# P08_eMMC.net
KiCad netlist of a schematic drawn in Altium Designer
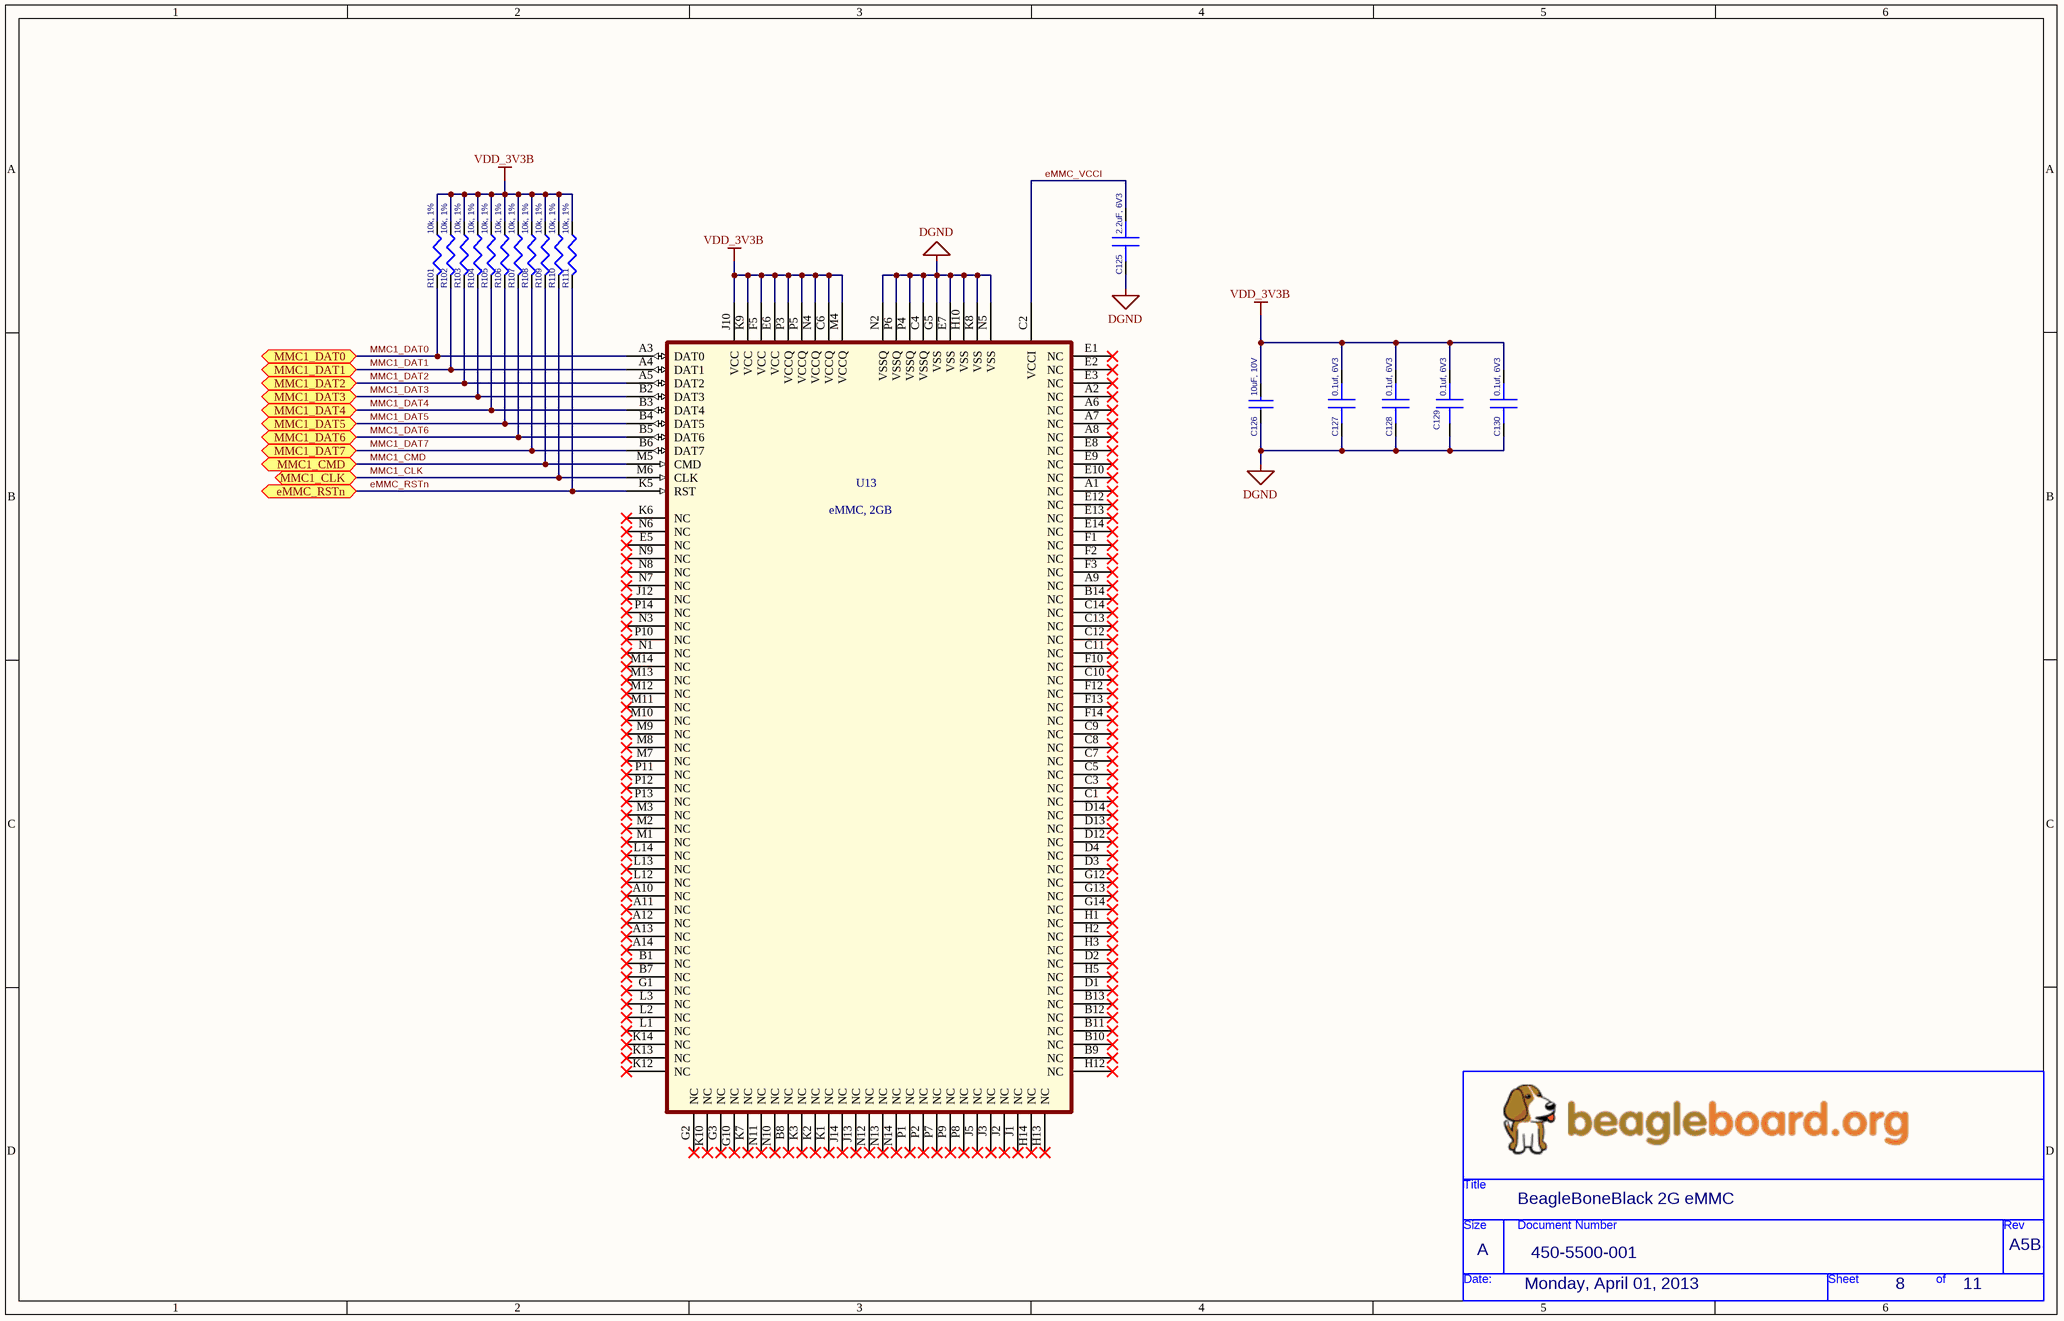
[diagram p0: P08_eMMC.SchDoc]

(export (version "E")
  (design (tool "Eeschema 10.0.6"))
  (components
    (comp (ref "C125")
      (value "2.2uF, 6V3")
      (footprint "402")
      (description "CAP CER 2.2UF 6.3V 10% X5R 0402")
      (fields
        (field (name "MANUFACTURER") "TDK Corporation")
        (field (name "MANUFACTURER PART NUMBER") "C1005X5R0J225K050BC")
      )
      (libsource (lib "BEAGLEBONEBLACK_REV A5B") (part "CAP SMD"))
    )
    (comp (ref "C126")
      (value "10uF, 10V")
      (footprint "805")
      (description "CAP CER 10UF 10V Y5V 0805")
      (fields
        (field (name "MANUFACTURER") "TDK Corporation")
        (field (name "MANUFACTURER PART NUMBER") "C2012Y5V1A106Z")
      )
      (libsource (lib "BEAGLEBONEBLACK_REV A5B") (part "CAP_4.7uF_X5R_6.3V_10%_0603"))
    )
    (comp (ref "C127")
      (value "0.1uf, 6V3")
      (footprint "402")
      (description "CAP CER 0.1UF 6.3V 10% X5R 0402")
      (fields
        (field (name "MANUFACTURER") "TDK Corporation")
        (field (name "MANUFACTURER PART NUMBER") "C1005X5R0J104K050BA")
      )
      (libsource (lib "BEAGLEBONEBLACK_REV A5B") (part "CAP SMD"))
    )
    (comp (ref "C128")
      (value "0.1uf, 6V3")
      (footprint "402")
      (description "CAP CER 0.1UF 6.3V 10% X5R 0402")
      (fields
        (field (name "MANUFACTURER") "TDK Corporation")
        (field (name "MANUFACTURER PART NUMBER") "C1005X5R0J104K050BA")
      )
      (libsource (lib "BEAGLEBONEBLACK_REV A5B") (part "CAP SMD"))
    )
    (comp (ref "C129")
      (value "0.1uf, 6V3")
      (footprint "402")
      (description "CAP CER 0.1UF 6.3V 10% X5R 0402")
      (fields
        (field (name "MANUFACTURER") "TDK Corporation")
        (field (name "MANUFACTURER PART NUMBER") "C1005X5R0J104K050BA")
      )
      (libsource (lib "BEAGLEBONEBLACK_REV A5B") (part "CAP SMD"))
    )
    (comp (ref "C130")
      (value "0.1uf, 6V3")
      (footprint "402")
      (description "CAP CER 0.1UF 6.3V 10% X5R 0402")
      (fields
        (field (name "MANUFACTURER") "TDK Corporation")
        (field (name "MANUFACTURER PART NUMBER") "C1005X5R0J104K050BA")
      )
      (libsource (lib "BEAGLEBONEBLACK_REV A5B") (part "CAP SMD"))
    )
    (comp (ref "R101")
      (value "10k, 1%")
      (footprint "402")
      (description "RES 10K OHM 1/16W 5% 0402 SMD")
      (fields
        (field (name "MANUFACTURER") "Rohm Semiconductor")
        (field (name "MANUFACTURER PART NUMBER") "MCR01MZPJ103")
      )
      (libsource (lib "BEAGLEBONEBLACK_REV A5B") (part "RES_10K_1/16W_1%_0402"))
    )
    (comp (ref "R102")
      (value "10k, 1%")
      (footprint "402")
      (description "RES 10K OHM 1/16W 5% 0402 SMD")
      (fields
        (field (name "MANUFACTURER") "Rohm Semiconductor")
        (field (name "MANUFACTURER PART NUMBER") "MCR01MZPJ103")
      )
      (libsource (lib "BEAGLEBONEBLACK_REV A5B") (part "RES_10K_1/16W_1%_0402"))
    )
    (comp (ref "R103")
      (value "10k, 1%")
      (footprint "402")
      (description "RES 10K OHM 1/16W 5% 0402 SMD")
      (fields
        (field (name "MANUFACTURER") "Rohm Semiconductor")
        (field (name "MANUFACTURER PART NUMBER") "MCR01MZPJ103")
      )
      (libsource (lib "BEAGLEBONEBLACK_REV A5B") (part "RES_10K_1/16W_1%_0402"))
    )
    (comp (ref "R104")
      (value "10k, 1%")
      (footprint "402")
      (description "RES 10K OHM 1/16W 5% 0402 SMD")
      (fields
        (field (name "MANUFACTURER") "Rohm Semiconductor")
        (field (name "MANUFACTURER PART NUMBER") "MCR01MZPJ103")
      )
      (libsource (lib "BEAGLEBONEBLACK_REV A5B") (part "RES_10K_1/16W_1%_0402"))
    )
    (comp (ref "R105")
      (value "10k, 1%")
      (footprint "402")
      (description "RES 10K OHM 1/16W 5% 0402 SMD")
      (fields
        (field (name "MANUFACTURER") "Rohm Semiconductor")
        (field (name "MANUFACTURER PART NUMBER") "MCR01MZPJ103")
      )
      (libsource (lib "BEAGLEBONEBLACK_REV A5B") (part "RES_10K_1/16W_1%_0402"))
    )
    (comp (ref "R106")
      (value "10k, 1%")
      (footprint "402")
      (description "RES 10K OHM 1/16W 5% 0402 SMD")
      (fields
        (field (name "MANUFACTURER") "Rohm Semiconductor")
        (field (name "MANUFACTURER PART NUMBER") "MCR01MZPJ103")
      )
      (libsource (lib "BEAGLEBONEBLACK_REV A5B") (part "RES_10K_1/16W_1%_0402"))
    )
    (comp (ref "R107")
      (value "10k, 1%")
      (footprint "402")
      (description "RES 10K OHM 1/16W 5% 0402 SMD")
      (fields
        (field (name "MANUFACTURER") "Rohm Semiconductor")
        (field (name "MANUFACTURER PART NUMBER") "MCR01MZPJ103")
      )
      (libsource (lib "BEAGLEBONEBLACK_REV A5B") (part "RES_10K_1/16W_1%_0402"))
    )
    (comp (ref "R108")
      (value "10k, 1%")
      (footprint "402")
      (description "RES 10K OHM 1/16W 5% 0402 SMD")
      (fields
        (field (name "MANUFACTURER") "Rohm Semiconductor")
        (field (name "MANUFACTURER PART NUMBER") "MCR01MZPJ103")
      )
      (libsource (lib "BEAGLEBONEBLACK_REV A5B") (part "RES_10K_1/16W_1%_0402"))
    )
    (comp (ref "R109")
      (value "10k, 1%")
      (footprint "402")
      (description "RES 10K OHM 1/16W 5% 0402 SMD")
      (fields
        (field (name "MANUFACTURER") "Rohm Semiconductor")
        (field (name "MANUFACTURER PART NUMBER") "MCR01MZPJ103")
      )
      (libsource (lib "BEAGLEBONEBLACK_REV A5B") (part "RES_10K_1/16W_1%_0402"))
    )
    (comp (ref "R110")
      (value "10k, 1%")
      (footprint "402")
      (description "RES 10K OHM 1/16W 5% 0402 SMD")
      (fields
        (field (name "MANUFACTURER") "Rohm Semiconductor")
        (field (name "MANUFACTURER PART NUMBER") "MCR01MZPJ103")
      )
      (libsource (lib "BEAGLEBONEBLACK_REV A5B") (part "RES_10K_1/16W_1%_0402"))
    )
    (comp (ref "R111")
      (value "10k, 1%")
      (footprint "402")
      (description "RES 10K OHM 1/16W 5% 0402 SMD")
      (fields
        (field (name "MANUFACTURER") "Rohm Semiconductor")
        (field (name "MANUFACTURER PART NUMBER") "MCR01MZPJ103")
      )
      (libsource (lib "BEAGLEBONEBLACK_REV A5B") (part "RES_10K_1/16W_1%_0402"))
    )
    (comp (ref "U13")
      (value "eMMC, 2GB")
      (footprint "BGA153_P14_P5_11P5X13")
      (description "Flash Card 2G-byte 3.3V MultiMedia Card 153-Pin WFBGA")
      (fields
        (field (name "MANUFACTURER") "Micron Technology")
        (field (name "MANUFACTURER PART NUMBER") "MTFC2GMVEA-0M WT")
      )
      (libsource (lib "BEAGLEBONEBLACK_REV A5B") (part "eMMC"))
    )
  )
  (nets
    (net (code "1") (name "/MMC1_CLK") (class "Default")
      (node (ref "R110") (pin "2") (pinfunction "2_2") (pintype "passive"))
      (node (ref "U13") (pin "M6") (pinfunction "CLK_M6") (pintype "input"))
    )
    (net (code "2") (name "/MMC1_CMD") (class "Default")
      (node (ref "R109") (pin "2") (pinfunction "2_2") (pintype "passive"))
      (node (ref "U13") (pin "M5") (pinfunction "CMD_M5") (pintype "input"))
    )
    (net (code "3") (name "/MMC1_DAT0") (class "Default")
      (node (ref "R101") (pin "2") (pinfunction "2_2") (pintype "passive"))
      (node (ref "U13") (pin "A3") (pinfunction "DAT0_A3") (pintype "bidirectional"))
    )
    (net (code "4") (name "/MMC1_DAT1") (class "Default")
      (node (ref "R102") (pin "2") (pinfunction "2_2") (pintype "passive"))
      (node (ref "U13") (pin "A4") (pinfunction "DAT1_A4") (pintype "bidirectional"))
    )
    (net (code "5") (name "/MMC1_DAT2") (class "Default")
      (node (ref "R103") (pin "2") (pinfunction "2_2") (pintype "passive"))
      (node (ref "U13") (pin "A5") (pinfunction "DAT2_A5") (pintype "bidirectional"))
    )
    (net (code "6") (name "/MMC1_DAT3") (class "Default")
      (node (ref "R104") (pin "2") (pinfunction "2_2") (pintype "passive"))
      (node (ref "U13") (pin "B2") (pinfunction "DAT3_B2") (pintype "bidirectional"))
    )
    (net (code "7") (name "/MMC1_DAT4") (class "Default")
      (node (ref "R105") (pin "2") (pinfunction "2_2") (pintype "passive"))
      (node (ref "U13") (pin "B3") (pinfunction "DAT4_B3") (pintype "bidirectional"))
    )
    (net (code "8") (name "/MMC1_DAT5") (class "Default")
      (node (ref "R106") (pin "2") (pinfunction "2_2") (pintype "passive"))
      (node (ref "U13") (pin "B4") (pinfunction "DAT5_B4") (pintype "bidirectional"))
    )
    (net (code "9") (name "/MMC1_DAT6") (class "Default")
      (node (ref "R107") (pin "2") (pinfunction "2_2") (pintype "passive"))
      (node (ref "U13") (pin "B5") (pinfunction "DAT6_B5") (pintype "bidirectional"))
    )
    (net (code "10") (name "/MMC1_DAT7") (class "Default")
      (node (ref "R108") (pin "2") (pinfunction "2_2") (pintype "passive"))
      (node (ref "U13") (pin "B6") (pinfunction "DAT7_B6") (pintype "bidirectional"))
    )
    (net (code "11") (name "/eMMC_RSTn") (class "Default")
      (node (ref "R111") (pin "2") (pinfunction "2_2") (pintype "passive"))
      (node (ref "U13") (pin "K5") (pinfunction "RST_K5") (pintype "input"))
    )
    (net (code "12") (name "/eMMC_VCCI") (class "Default")
      (node (ref "C125") (pin "1") (pinfunction "1_1") (pintype "passive"))
      (node (ref "U13") (pin "C2") (pinfunction "VCCI_C2") (pintype "power_in"))
    )
    (net (code "13") (name "DGND") (class "Default")
      (node (ref "C125") (pin "2") (pinfunction "2_2") (pintype "passive"))
      (node (ref "C126") (pin "1") (pinfunction "1_1") (pintype "passive"))
      (node (ref "C127") (pin "2") (pinfunction "2_2") (pintype "passive"))
      (node (ref "C128") (pin "2") (pinfunction "2_2") (pintype "passive"))
      (node (ref "C129") (pin "2") (pinfunction "2_2") (pintype "passive"))
      (node (ref "C130") (pin "2") (pinfunction "2_2") (pintype "passive"))
      (node (ref "U13") (pin "C4") (pinfunction "VSSQ_C4") (pintype "power_in"))
      (node (ref "U13") (pin "E7") (pinfunction "VSS_E7") (pintype "power_in"))
      (node (ref "U13") (pin "G5") (pinfunction "VSS_G5") (pintype "power_in"))
      (node (ref "U13") (pin "H10") (pinfunction "VSS_H10") (pintype "power_in"))
      (node (ref "U13") (pin "K8") (pinfunction "VSS_K8") (pintype "power_in"))
      (node (ref "U13") (pin "N2") (pinfunction "VSSQ_N2") (pintype "power_in"))
      (node (ref "U13") (pin "N5") (pinfunction "VSS_N5") (pintype "power_in"))
      (node (ref "U13") (pin "P4") (pinfunction "VSSQ_P4") (pintype "power_in"))
      (node (ref "U13") (pin "P6") (pinfunction "VSSQ_P6") (pintype "power_in"))
    )
    (net (code "14") (name "VDD_3V3B") (class "Default")
      (node (ref "C126") (pin "2") (pinfunction "2_2") (pintype "passive"))
      (node (ref "C127") (pin "1") (pinfunction "1_1") (pintype "passive"))
      (node (ref "C128") (pin "1") (pinfunction "1_1") (pintype "passive"))
      (node (ref "C129") (pin "1") (pinfunction "1_1") (pintype "passive"))
      (node (ref "C130") (pin "1") (pinfunction "1_1") (pintype "passive"))
      (node (ref "R101") (pin "1") (pinfunction "1_1") (pintype "passive"))
      (node (ref "R102") (pin "1") (pinfunction "1_1") (pintype "passive"))
      (node (ref "R103") (pin "1") (pinfunction "1_1") (pintype "passive"))
      (node (ref "R104") (pin "1") (pinfunction "1_1") (pintype "passive"))
      (node (ref "R105") (pin "1") (pinfunction "1_1") (pintype "passive"))
      (node (ref "R106") (pin "1") (pinfunction "1_1") (pintype "passive"))
      (node (ref "R107") (pin "1") (pinfunction "1_1") (pintype "passive"))
      (node (ref "R108") (pin "1") (pinfunction "1_1") (pintype "passive"))
      (node (ref "R109") (pin "1") (pinfunction "1_1") (pintype "passive"))
      (node (ref "R110") (pin "1") (pinfunction "1_1") (pintype "passive"))
      (node (ref "R111") (pin "1") (pinfunction "1_1") (pintype "passive"))
      (node (ref "U13") (pin "C6") (pinfunction "VCCQ_C6") (pintype "power_in"))
      (node (ref "U13") (pin "E6") (pinfunction "VCC_E6") (pintype "power_in"))
      (node (ref "U13") (pin "F5") (pinfunction "VCC_F5") (pintype "power_in"))
      (node (ref "U13") (pin "J10") (pinfunction "VCC_J10") (pintype "power_in"))
      (node (ref "U13") (pin "K9") (pinfunction "VCC_K9") (pintype "power_in"))
      (node (ref "U13") (pin "M4") (pinfunction "VCCQ_M4") (pintype "power_in"))
      (node (ref "U13") (pin "N4") (pinfunction "VCCQ_N4") (pintype "power_in"))
      (node (ref "U13") (pin "P3") (pinfunction "VCCQ_P3") (pintype "power_in"))
      (node (ref "U13") (pin "P5") (pinfunction "VCCQ_P5") (pintype "power_in"))
    )
    (net (code "15") (name "unconnected-(U13-NC-PadA1)") (class "Default")
      (node (ref "U13") (pin "A1") (pinfunction "NC_A1") (pintype "passive+no_connect"))
    )
    (net (code "16") (name "unconnected-(U13-NC-PadA2)") (class "Default")
      (node (ref "U13") (pin "A2") (pinfunction "NC_A2") (pintype "passive+no_connect"))
    )
    (net (code "17") (name "unconnected-(U13-NC-PadA6)") (class "Default")
      (node (ref "U13") (pin "A6") (pinfunction "NC_A6") (pintype "passive+no_connect"))
    )
    (net (code "18") (name "unconnected-(U13-NC-PadA7)") (class "Default")
      (node (ref "U13") (pin "A7") (pinfunction "NC_A7") (pintype "passive+no_connect"))
    )
    (net (code "19") (name "unconnected-(U13-NC-PadA8)") (class "Default")
      (node (ref "U13") (pin "A8") (pinfunction "NC_A8") (pintype "passive+no_connect"))
    )
    (net (code "20") (name "unconnected-(U13-NC-PadA9)") (class "Default")
      (node (ref "U13") (pin "A9") (pinfunction "NC_A9") (pintype "passive+no_connect"))
    )
    (net (code "21") (name "unconnected-(U13-NC-PadA10)") (class "Default")
      (node (ref "U13") (pin "A10") (pinfunction "NC_A10") (pintype "passive+no_connect"))
    )
    (net (code "22") (name "unconnected-(U13-NC-PadA11)") (class "Default")
      (node (ref "U13") (pin "A11") (pinfunction "NC_A11") (pintype "passive+no_connect"))
    )
    (net (code "23") (name "unconnected-(U13-NC-PadA12)") (class "Default")
      (node (ref "U13") (pin "A12") (pinfunction "NC_A12") (pintype "passive+no_connect"))
    )
    (net (code "24") (name "unconnected-(U13-NC-PadA13)") (class "Default")
      (node (ref "U13") (pin "A13") (pinfunction "NC_A13") (pintype "passive+no_connect"))
    )
    (net (code "25") (name "unconnected-(U13-NC-PadA14)") (class "Default")
      (node (ref "U13") (pin "A14") (pinfunction "NC_A14") (pintype "passive+no_connect"))
    )
    (net (code "26") (name "unconnected-(U13-NC-PadB1)") (class "Default")
      (node (ref "U13") (pin "B1") (pinfunction "NC_B1") (pintype "passive+no_connect"))
    )
    (net (code "27") (name "unconnected-(U13-NC-PadB7)") (class "Default")
      (node (ref "U13") (pin "B7") (pinfunction "NC_B7") (pintype "passive+no_connect"))
    )
    (net (code "28") (name "unconnected-(U13-NC-PadB8)") (class "Default")
      (node (ref "U13") (pin "B8") (pinfunction "NC_B8") (pintype "passive+no_connect"))
    )
    (net (code "29") (name "unconnected-(U13-NC-PadB9)") (class "Default")
      (node (ref "U13") (pin "B9") (pinfunction "NC_B9") (pintype "passive+no_connect"))
    )
    (net (code "30") (name "unconnected-(U13-NC-PadB10)") (class "Default")
      (node (ref "U13") (pin "B10") (pinfunction "NC_B10") (pintype "passive+no_connect"))
    )
    (net (code "31") (name "unconnected-(U13-NC-PadB11)") (class "Default")
      (node (ref "U13") (pin "B11") (pinfunction "NC_B11") (pintype "passive+no_connect"))
    )
    (net (code "32") (name "unconnected-(U13-NC-PadB12)") (class "Default")
      (node (ref "U13") (pin "B12") (pinfunction "NC_B12") (pintype "passive+no_connect"))
    )
    (net (code "33") (name "unconnected-(U13-NC-PadB13)") (class "Default")
      (node (ref "U13") (pin "B13") (pinfunction "NC_B13") (pintype "passive+no_connect"))
    )
    (net (code "34") (name "unconnected-(U13-NC-PadB14)") (class "Default")
      (node (ref "U13") (pin "B14") (pinfunction "NC_B14") (pintype "passive+no_connect"))
    )
    (net (code "35") (name "unconnected-(U13-NC-PadC1)") (class "Default")
      (node (ref "U13") (pin "C1") (pinfunction "NC_C1") (pintype "passive+no_connect"))
    )
    (net (code "36") (name "unconnected-(U13-NC-PadC3)") (class "Default")
      (node (ref "U13") (pin "C3") (pinfunction "NC_C3") (pintype "passive+no_connect"))
    )
    (net (code "37") (name "unconnected-(U13-NC-PadC5)") (class "Default")
      (node (ref "U13") (pin "C5") (pinfunction "NC_C5") (pintype "passive+no_connect"))
    )
    (net (code "38") (name "unconnected-(U13-NC-PadC7)") (class "Default")
      (node (ref "U13") (pin "C7") (pinfunction "NC_C7") (pintype "passive+no_connect"))
    )
    (net (code "39") (name "unconnected-(U13-NC-PadC8)") (class "Default")
      (node (ref "U13") (pin "C8") (pinfunction "NC_C8") (pintype "passive+no_connect"))
    )
    (net (code "40") (name "unconnected-(U13-NC-PadC9)") (class "Default")
      (node (ref "U13") (pin "C9") (pinfunction "NC_C9") (pintype "passive+no_connect"))
    )
    (net (code "41") (name "unconnected-(U13-NC-PadC10)") (class "Default")
      (node (ref "U13") (pin "C10") (pinfunction "NC_C10") (pintype "passive+no_connect"))
    )
    (net (code "42") (name "unconnected-(U13-NC-PadC11)") (class "Default")
      (node (ref "U13") (pin "C11") (pinfunction "NC_C11") (pintype "passive+no_connect"))
    )
    (net (code "43") (name "unconnected-(U13-NC-PadC12)") (class "Default")
      (node (ref "U13") (pin "C12") (pinfunction "NC_C12") (pintype "passive+no_connect"))
    )
    (net (code "44") (name "unconnected-(U13-NC-PadC13)") (class "Default")
      (node (ref "U13") (pin "C13") (pinfunction "NC_C13") (pintype "passive+no_connect"))
    )
    (net (code "45") (name "unconnected-(U13-NC-PadC14)") (class "Default")
      (node (ref "U13") (pin "C14") (pinfunction "NC_C14") (pintype "passive+no_connect"))
    )
    (net (code "46") (name "unconnected-(U13-NC-PadD1)") (class "Default")
      (node (ref "U13") (pin "D1") (pinfunction "NC_D1") (pintype "passive+no_connect"))
    )
    (net (code "47") (name "unconnected-(U13-NC-PadD2)") (class "Default")
      (node (ref "U13") (pin "D2") (pinfunction "NC_D2") (pintype "passive+no_connect"))
    )
    (net (code "48") (name "unconnected-(U13-NC-PadD3)") (class "Default")
      (node (ref "U13") (pin "D3") (pinfunction "NC_D3") (pintype "passive+no_connect"))
    )
    (net (code "49") (name "unconnected-(U13-NC-PadD4)") (class "Default")
      (node (ref "U13") (pin "D4") (pinfunction "NC_D4") (pintype "passive+no_connect"))
    )
    (net (code "50") (name "unconnected-(U13-NC-PadD12)") (class "Default")
      (node (ref "U13") (pin "D12") (pinfunction "NC_D12") (pintype "passive+no_connect"))
    )
    (net (code "51") (name "unconnected-(U13-NC-PadD13)") (class "Default")
      (node (ref "U13") (pin "D13") (pinfunction "NC_D13") (pintype "passive+no_connect"))
    )
    (net (code "52") (name "unconnected-(U13-NC-PadD14)") (class "Default")
      (node (ref "U13") (pin "D14") (pinfunction "NC_D14") (pintype "passive+no_connect"))
    )
    (net (code "53") (name "unconnected-(U13-NC-PadE1)") (class "Default")
      (node (ref "U13") (pin "E1") (pinfunction "NC_E1") (pintype "passive+no_connect"))
    )
    (net (code "54") (name "unconnected-(U13-NC-PadE2)") (class "Default")
      (node (ref "U13") (pin "E2") (pinfunction "NC_E2") (pintype "passive+no_connect"))
    )
    (net (code "55") (name "unconnected-(U13-NC-PadE3)") (class "Default")
      (node (ref "U13") (pin "E3") (pinfunction "NC_E3") (pintype "passive+no_connect"))
    )
    (net (code "56") (name "unconnected-(U13-NC-PadE5)") (class "Default")
      (node (ref "U13") (pin "E5") (pinfunction "NC_E5") (pintype "passive+no_connect"))
    )
    (net (code "57") (name "unconnected-(U13-NC-PadE8)") (class "Default")
      (node (ref "U13") (pin "E8") (pinfunction "NC_E8") (pintype "passive+no_connect"))
    )
    (net (code "58") (name "unconnected-(U13-NC-PadE9)") (class "Default")
      (node (ref "U13") (pin "E9") (pinfunction "NC_E9") (pintype "passive+no_connect"))
    )
    (net (code "59") (name "unconnected-(U13-NC-PadE10)") (class "Default")
      (node (ref "U13") (pin "E10") (pinfunction "NC_E10") (pintype "passive+no_connect"))
    )
    (net (code "60") (name "unconnected-(U13-NC-PadE12)") (class "Default")
      (node (ref "U13") (pin "E12") (pinfunction "NC_E12") (pintype "passive+no_connect"))
    )
    (net (code "61") (name "unconnected-(U13-NC-PadE13)") (class "Default")
      (node (ref "U13") (pin "E13") (pinfunction "NC_E13") (pintype "passive+no_connect"))
    )
    (net (code "62") (name "unconnected-(U13-NC-PadE14)") (class "Default")
      (node (ref "U13") (pin "E14") (pinfunction "NC_E14") (pintype "passive+no_connect"))
    )
    (net (code "63") (name "unconnected-(U13-NC-PadF1)") (class "Default")
      (node (ref "U13") (pin "F1") (pinfunction "NC_F1") (pintype "passive+no_connect"))
    )
    (net (code "64") (name "unconnected-(U13-NC-PadF2)") (class "Default")
      (node (ref "U13") (pin "F2") (pinfunction "NC_F2") (pintype "passive+no_connect"))
    )
    (net (code "65") (name "unconnected-(U13-NC-PadF3)") (class "Default")
      (node (ref "U13") (pin "F3") (pinfunction "NC_F3") (pintype "passive+no_connect"))
    )
    (net (code "66") (name "unconnected-(U13-NC-PadF10)") (class "Default")
      (node (ref "U13") (pin "F10") (pinfunction "NC_F10") (pintype "passive+no_connect"))
    )
    (net (code "67") (name "unconnected-(U13-NC-PadF12)") (class "Default")
      (node (ref "U13") (pin "F12") (pinfunction "NC_F12") (pintype "passive+no_connect"))
    )
    (net (code "68") (name "unconnected-(U13-NC-PadF13)") (class "Default")
      (node (ref "U13") (pin "F13") (pinfunction "NC_F13") (pintype "passive+no_connect"))
    )
    (net (code "69") (name "unconnected-(U13-NC-PadF14)") (class "Default")
      (node (ref "U13") (pin "F14") (pinfunction "NC_F14") (pintype "passive+no_connect"))
    )
    (net (code "70") (name "unconnected-(U13-NC-PadG1)") (class "Default")
      (node (ref "U13") (pin "G1") (pinfunction "NC_G1") (pintype "passive+no_connect"))
    )
    (net (code "71") (name "unconnected-(U13-NC-PadG2)") (class "Default")
      (node (ref "U13") (pin "G2") (pinfunction "NC_G2") (pintype "passive+no_connect"))
    )
    (net (code "72") (name "unconnected-(U13-NC-PadG3)") (class "Default")
      (node (ref "U13") (pin "G3") (pinfunction "NC_G3") (pintype "passive+no_connect"))
    )
    (net (code "73") (name "unconnected-(U13-NC-PadG10)") (class "Default")
      (node (ref "U13") (pin "G10") (pinfunction "NC_G10") (pintype "passive+no_connect"))
    )
    (net (code "74") (name "unconnected-(U13-NC-PadG12)") (class "Default")
      (node (ref "U13") (pin "G12") (pinfunction "NC_G12") (pintype "passive+no_connect"))
    )
    (net (code "75") (name "unconnected-(U13-NC-PadG13)") (class "Default")
      (node (ref "U13") (pin "G13") (pinfunction "NC_G13") (pintype "passive+no_connect"))
    )
    (net (code "76") (name "unconnected-(U13-NC-PadG14)") (class "Default")
      (node (ref "U13") (pin "G14") (pinfunction "NC_G14") (pintype "passive+no_connect"))
    )
    (net (code "77") (name "unconnected-(U13-NC-PadH1)") (class "Default")
      (node (ref "U13") (pin "H1") (pinfunction "NC_H1") (pintype "passive+no_connect"))
    )
    (net (code "78") (name "unconnected-(U13-NC-PadH2)") (class "Default")
      (node (ref "U13") (pin "H2") (pinfunction "NC_H2") (pintype "passive+no_connect"))
    )
    (net (code "79") (name "unconnected-(U13-NC-PadH3)") (class "Default")
      (node (ref "U13") (pin "H3") (pinfunction "NC_H3") (pintype "passive+no_connect"))
    )
    (net (code "80") (name "unconnected-(U13-NC-PadH5)") (class "Default")
      (node (ref "U13") (pin "H5") (pinfunction "NC_H5") (pintype "passive+no_connect"))
    )
    (net (code "81") (name "unconnected-(U13-NC-PadH12)") (class "Default")
      (node (ref "U13") (pin "H12") (pinfunction "NC_H12") (pintype "passive+no_connect"))
    )
    (net (code "82") (name "unconnected-(U13-NC-PadH13)") (class "Default")
      (node (ref "U13") (pin "H13") (pinfunction "NC_H13") (pintype "passive+no_connect"))
    )
    (net (code "83") (name "unconnected-(U13-NC-PadH14)") (class "Default")
      (node (ref "U13") (pin "H14") (pinfunction "NC_H14") (pintype "passive+no_connect"))
    )
    (net (code "84") (name "unconnected-(U13-NC-PadJ1)") (class "Default")
      (node (ref "U13") (pin "J1") (pinfunction "NC_J1") (pintype "passive+no_connect"))
    )
    (net (code "85") (name "unconnected-(U13-NC-PadJ2)") (class "Default")
      (node (ref "U13") (pin "J2") (pinfunction "NC_J2") (pintype "passive+no_connect"))
    )
    (net (code "86") (name "unconnected-(U13-NC-PadJ3)") (class "Default")
      (node (ref "U13") (pin "J3") (pinfunction "NC_J3") (pintype "passive+no_connect"))
    )
    (net (code "87") (name "unconnected-(U13-NC-PadJ5)") (class "Default")
      (node (ref "U13") (pin "J5") (pinfunction "NC_J5") (pintype "passive+no_connect"))
    )
    (net (code "88") (name "unconnected-(U13-NC-PadJ12)") (class "Default")
      (node (ref "U13") (pin "J12") (pinfunction "NC_J12") (pintype "passive+no_connect"))
    )
    (net (code "89") (name "unconnected-(U13-NC-PadJ13)") (class "Default")
      (node (ref "U13") (pin "J13") (pinfunction "NC_J13") (pintype "passive+no_connect"))
    )
    (net (code "90") (name "unconnected-(U13-NC-PadJ14)") (class "Default")
      (node (ref "U13") (pin "J14") (pinfunction "NC_J14") (pintype "passive+no_connect"))
    )
    (net (code "91") (name "unconnected-(U13-NC-PadK1)") (class "Default")
      (node (ref "U13") (pin "K1") (pinfunction "NC_K1") (pintype "passive+no_connect"))
    )
    (net (code "92") (name "unconnected-(U13-NC-PadK2)") (class "Default")
      (node (ref "U13") (pin "K2") (pinfunction "NC_K2") (pintype "passive+no_connect"))
    )
    (net (code "93") (name "unconnected-(U13-NC-PadK3)") (class "Default")
      (node (ref "U13") (pin "K3") (pinfunction "NC_K3") (pintype "passive+no_connect"))
    )
    (net (code "94") (name "unconnected-(U13-NC-PadK6)") (class "Default")
      (node (ref "U13") (pin "K6") (pinfunction "NC_K6") (pintype "passive+no_connect"))
    )
    (net (code "95") (name "unconnected-(U13-NC-PadK7)") (class "Default")
      (node (ref "U13") (pin "K7") (pinfunction "NC_K7") (pintype "passive+no_connect"))
    )
    (net (code "96") (name "unconnected-(U13-NC-PadK10)") (class "Default")
      (node (ref "U13") (pin "K10") (pinfunction "NC_K10") (pintype "passive+no_connect"))
    )
    (net (code "97") (name "unconnected-(U13-NC-PadK12)") (class "Default")
      (node (ref "U13") (pin "K12") (pinfunction "NC_K12") (pintype "passive+no_connect"))
    )
    (net (code "98") (name "unconnected-(U13-NC-PadK13)") (class "Default")
      (node (ref "U13") (pin "K13") (pinfunction "NC_K13") (pintype "passive+no_connect"))
    )
    (net (code "99") (name "unconnected-(U13-NC-PadK14)") (class "Default")
      (node (ref "U13") (pin "K14") (pinfunction "NC_K14") (pintype "passive+no_connect"))
    )
    (net (code "100") (name "unconnected-(U13-NC-PadL1)") (class "Default")
      (node (ref "U13") (pin "L1") (pinfunction "NC_L1") (pintype "passive+no_connect"))
    )
    (net (code "101") (name "unconnected-(U13-NC-PadL2)") (class "Default")
      (node (ref "U13") (pin "L2") (pinfunction "NC_L2") (pintype "passive+no_connect"))
    )
    (net (code "102") (name "unconnected-(U13-NC-PadL3)") (class "Default")
      (node (ref "U13") (pin "L3") (pinfunction "NC_L3") (pintype "passive+no_connect"))
    )
    (net (code "103") (name "unconnected-(U13-NC-PadL12)") (class "Default")
      (node (ref "U13") (pin "L12") (pinfunction "NC_L12") (pintype "passive+no_connect"))
    )
    (net (code "104") (name "unconnected-(U13-NC-PadL13)") (class "Default")
      (node (ref "U13") (pin "L13") (pinfunction "NC_L13") (pintype "passive+no_connect"))
    )
    (net (code "105") (name "unconnected-(U13-NC-PadL14)") (class "Default")
      (node (ref "U13") (pin "L14") (pinfunction "NC_L14") (pintype "passive+no_connect"))
    )
    (net (code "106") (name "unconnected-(U13-NC-PadM1)") (class "Default")
      (node (ref "U13") (pin "M1") (pinfunction "NC_M1") (pintype "passive+no_connect"))
    )
    (net (code "107") (name "unconnected-(U13-NC-PadM2)") (class "Default")
      (node (ref "U13") (pin "M2") (pinfunction "NC_M2") (pintype "passive+no_connect"))
    )
    (net (code "108") (name "unconnected-(U13-NC-PadM3)") (class "Default")
      (node (ref "U13") (pin "M3") (pinfunction "NC_M3") (pintype "passive+no_connect"))
    )
    (net (code "109") (name "unconnected-(U13-NC-PadM7)") (class "Default")
      (node (ref "U13") (pin "M7") (pinfunction "NC_M7") (pintype "passive+no_connect"))
    )
    (net (code "110") (name "unconnected-(U13-NC-PadM8)") (class "Default")
      (node (ref "U13") (pin "M8") (pinfunction "NC_M8") (pintype "passive+no_connect"))
    )
    (net (code "111") (name "unconnected-(U13-NC-PadM9)") (class "Default")
      (node (ref "U13") (pin "M9") (pinfunction "NC_M9") (pintype "passive+no_connect"))
    )
    (net (code "112") (name "unconnected-(U13-NC-PadM10)") (class "Default")
      (node (ref "U13") (pin "M10") (pinfunction "NC_M10") (pintype "passive+no_connect"))
    )
    (net (code "113") (name "unconnected-(U13-NC-PadM11)") (class "Default")
      (node (ref "U13") (pin "M11") (pinfunction "NC_M11") (pintype "passive+no_connect"))
    )
    (net (code "114") (name "unconnected-(U13-NC-PadM12)") (class "Default")
      (node (ref "U13") (pin "M12") (pinfunction "NC_M12") (pintype "passive+no_connect"))
    )
    (net (code "115") (name "unconnected-(U13-NC-PadM13)") (class "Default")
      (node (ref "U13") (pin "M13") (pinfunction "NC_M13") (pintype "passive+no_connect"))
    )
    (net (code "116") (name "unconnected-(U13-NC-PadM14)") (class "Default")
      (node (ref "U13") (pin "M14") (pinfunction "NC_M14") (pintype "passive+no_connect"))
    )
    (net (code "117") (name "unconnected-(U13-NC-PadN1)") (class "Default")
      (node (ref "U13") (pin "N1") (pinfunction "NC_N1") (pintype "passive+no_connect"))
    )
    (net (code "118") (name "unconnected-(U13-NC-PadN3)") (class "Default")
      (node (ref "U13") (pin "N3") (pinfunction "NC_N3") (pintype "passive+no_connect"))
    )
    (net (code "119") (name "unconnected-(U13-NC-PadN6)") (class "Default")
      (node (ref "U13") (pin "N6") (pinfunction "NC_N6") (pintype "passive+no_connect"))
    )
    (net (code "120") (name "unconnected-(U13-NC-PadN7)") (class "Default")
      (node (ref "U13") (pin "N7") (pinfunction "NC_N7") (pintype "passive+no_connect"))
    )
    (net (code "121") (name "unconnected-(U13-NC-PadN8)") (class "Default")
      (node (ref "U13") (pin "N8") (pinfunction "NC_N8") (pintype "passive+no_connect"))
    )
    (net (code "122") (name "unconnected-(U13-NC-PadN9)") (class "Default")
      (node (ref "U13") (pin "N9") (pinfunction "NC_N9") (pintype "passive+no_connect"))
    )
    (net (code "123") (name "unconnected-(U13-NC-PadN10)") (class "Default")
      (node (ref "U13") (pin "N10") (pinfunction "NC_N10") (pintype "passive+no_connect"))
    )
    (net (code "124") (name "unconnected-(U13-NC-PadN11)") (class "Default")
      (node (ref "U13") (pin "N11") (pinfunction "NC_N11") (pintype "passive+no_connect"))
    )
    (net (code "125") (name "unconnected-(U13-NC-PadN12)") (class "Default")
      (node (ref "U13") (pin "N12") (pinfunction "NC_N12") (pintype "passive+no_connect"))
    )
    (net (code "126") (name "unconnected-(U13-NC-PadN13)") (class "Default")
      (node (ref "U13") (pin "N13") (pinfunction "NC_N13") (pintype "passive+no_connect"))
    )
    (net (code "127") (name "unconnected-(U13-NC-PadN14)") (class "Default")
      (node (ref "U13") (pin "N14") (pinfunction "NC_N14") (pintype "passive+no_connect"))
    )
    (net (code "128") (name "unconnected-(U13-NC-PadP1)") (class "Default")
      (node (ref "U13") (pin "P1") (pinfunction "NC_P1") (pintype "passive+no_connect"))
    )
    (net (code "129") (name "unconnected-(U13-NC-PadP2)") (class "Default")
      (node (ref "U13") (pin "P2") (pinfunction "NC_P2") (pintype "passive+no_connect"))
    )
    (net (code "130") (name "unconnected-(U13-NC-PadP7)") (class "Default")
      (node (ref "U13") (pin "P7") (pinfunction "NC_P7") (pintype "passive+no_connect"))
    )
    (net (code "131") (name "unconnected-(U13-NC-PadP8)") (class "Default")
      (node (ref "U13") (pin "P8") (pinfunction "NC_P8") (pintype "passive+no_connect"))
    )
    (net (code "132") (name "unconnected-(U13-NC-PadP9)") (class "Default")
      (node (ref "U13") (pin "P9") (pinfunction "NC_P9") (pintype "passive+no_connect"))
    )
    (net (code "133") (name "unconnected-(U13-NC-PadP10)") (class "Default")
      (node (ref "U13") (pin "P10") (pinfunction "NC_P10") (pintype "passive+no_connect"))
    )
    (net (code "134") (name "unconnected-(U13-NC-PadP11)") (class "Default")
      (node (ref "U13") (pin "P11") (pinfunction "NC_P11") (pintype "passive+no_connect"))
    )
    (net (code "135") (name "unconnected-(U13-NC-PadP12)") (class "Default")
      (node (ref "U13") (pin "P12") (pinfunction "NC_P12") (pintype "passive+no_connect"))
    )
    (net (code "136") (name "unconnected-(U13-NC-PadP13)") (class "Default")
      (node (ref "U13") (pin "P13") (pinfunction "NC_P13") (pintype "passive+no_connect"))
    )
    (net (code "137") (name "unconnected-(U13-NC-PadP14)") (class "Default")
      (node (ref "U13") (pin "P14") (pinfunction "NC_P14") (pintype "passive+no_connect"))
    )
  )
)
